# design.net
KiCad netlist of a schematic drawn in Altium Designer
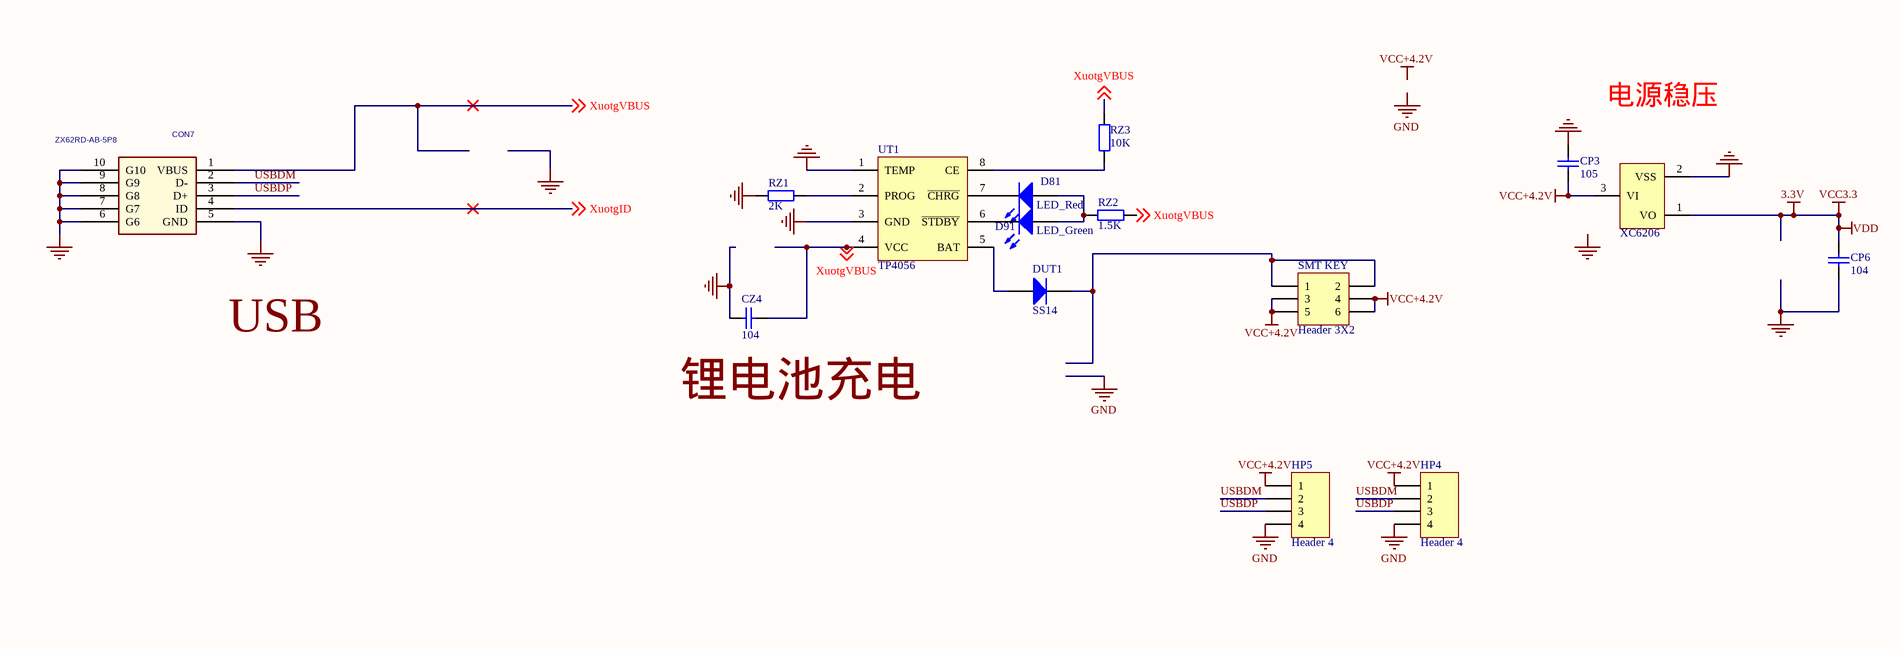
[diagram p0: 智能笔.SchDoc, top left]
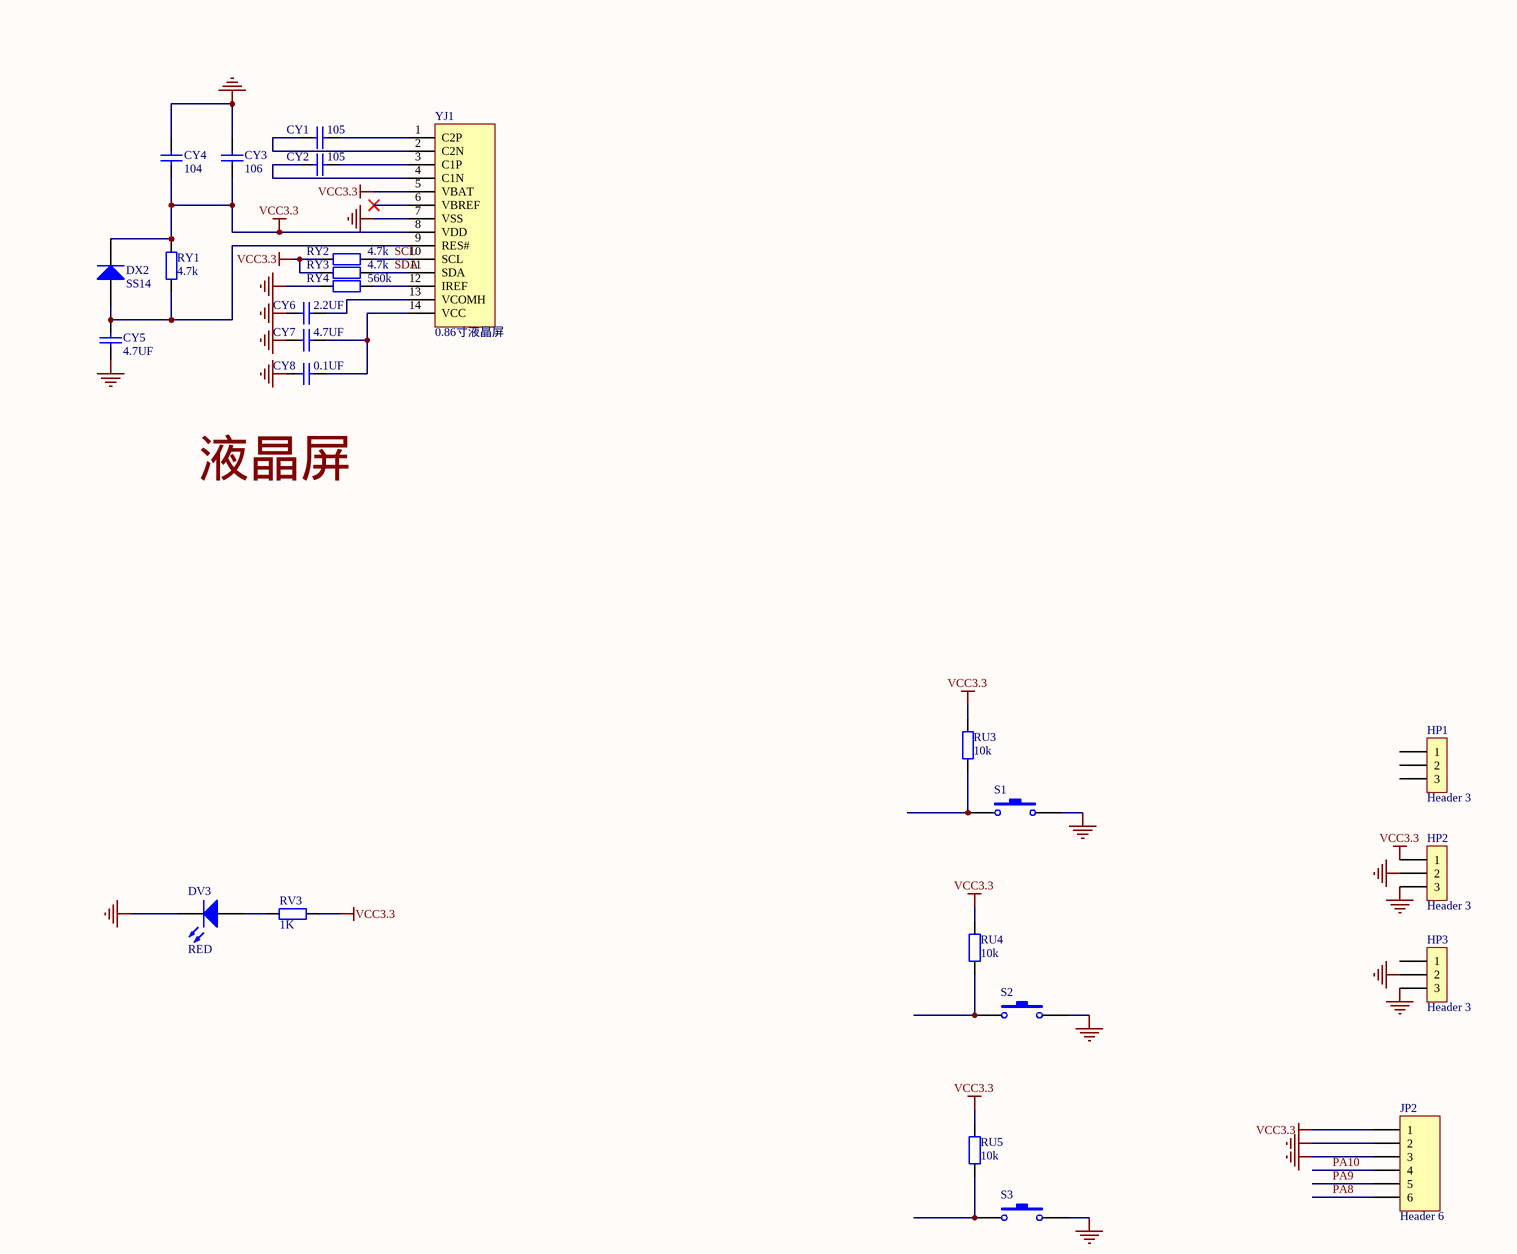
[diagram p1: 智能笔.SchDoc, top right]
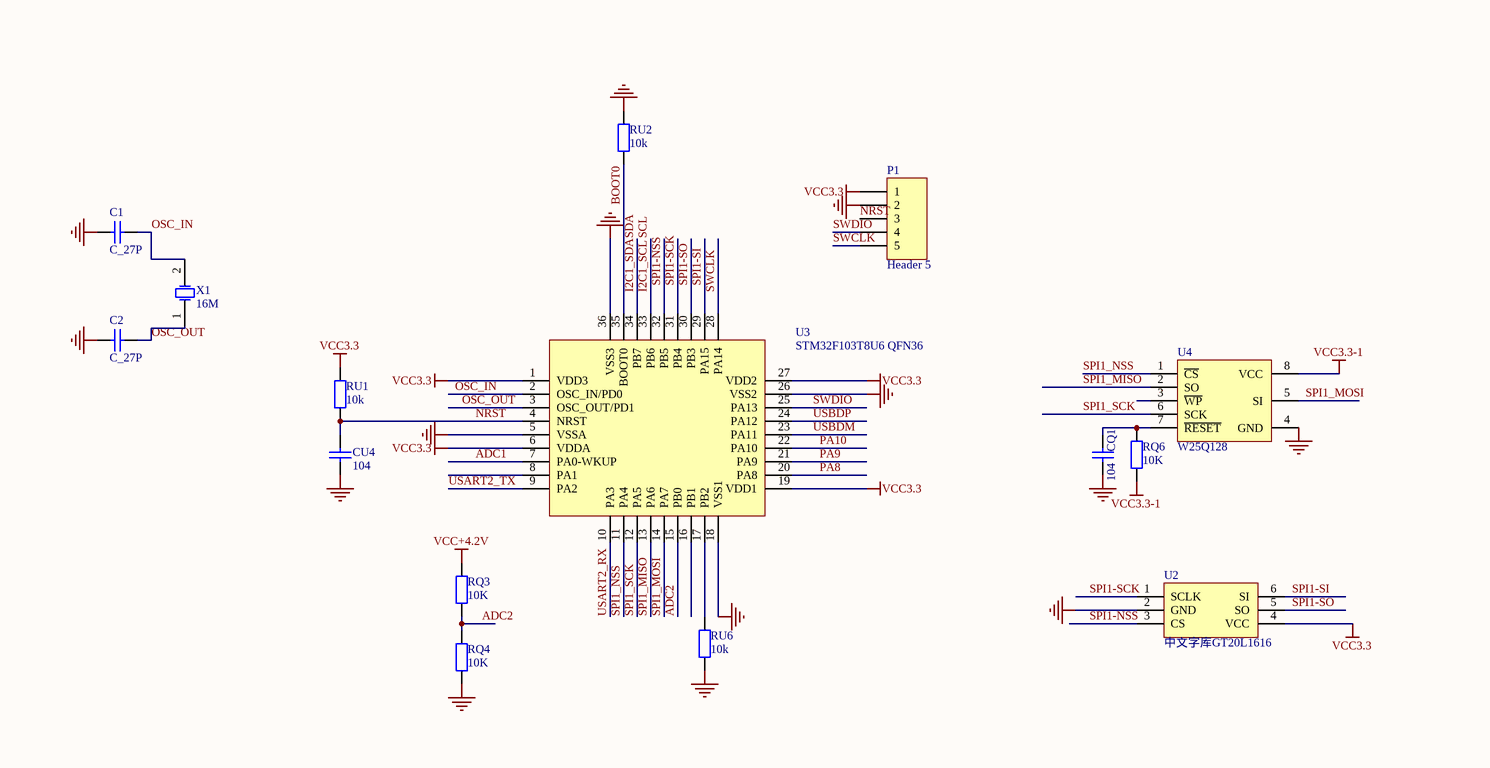
[diagram p2: 智能笔.SchDoc, bottom left]

(export (version "E")
  (design (tool "Eeschema 10.0.6"))
  (components
    (comp (ref "C1")
      (value "C_27P")
      (footprint "0402")
      (description "Capacitor")
      (fields (field (name "PUBLISHER") "Altium Limited"))
      (libsource (lib "Miscellaneous Devices") (part "Cap"))
    )
    (comp (ref "C2")
      (value "C_27P")
      (footprint "0402")
      (description "Capacitor")
      (fields (field (name "PUBLISHER") "Altium Limited"))
      (libsource (lib "Miscellaneous Devices") (part "Cap"))
    )
    (comp (ref "CON7")
      (value "ZX62RD-AB-5P8")
      (footprint "MICROUSB-B-H4")
      (libsource (lib "*") (part "ZX62RD-AB-5P8_4"))
    )
    (comp (ref "CP3")
      (value "105")
      (footprint "0402")
      (description "Capacitor")
      (fields (field (name "PUBLISHER") "Altium Limited"))
      (libsource (lib "原理图库") (part "104"))
    )
    (comp (ref "CP6")
      (value "104")
      (footprint "0402")
      (description "Capacitor")
      (fields (field (name "PUBLISHER") "Altium Limited"))
      (libsource (lib "Miscellaneous Devices") (part "Cap"))
    )
    (comp (ref "CQ1")
      (value "104")
      (footprint "0402")
      (description "Capacitor")
      (fields (field (name "PUBLISHER") "Altium Limited"))
      (libsource (lib "原理图库") (part "104"))
    )
    (comp (ref "CU4")
      (value "104")
      (footprint "0402")
      (description "Capacitor")
      (fields (field (name "PUBLISHER") "Altium Limited"))
      (libsource (lib "Miscellaneous Devices") (part "Cap"))
    )
    (comp (ref "CY1")
      (value "105")
      (footprint "0402")
      (description "Capacitor")
      (fields (field (name "PUBLISHER") "Altium Limited"))
      (libsource (lib "原理图库") (part "104"))
    )
    (comp (ref "CY2")
      (value "105")
      (footprint "0402")
      (description "Capacitor")
      (fields (field (name "PUBLISHER") "Altium Limited"))
      (libsource (lib "原理图库") (part "104"))
    )
    (comp (ref "CY3")
      (value "106")
      (footprint "0603-1")
      (description "Capacitor")
      (fields (field (name "PUBLISHER") "Altium Limited"))
      (libsource (lib "Miscellaneous Devices") (part "Cap"))
    )
    (comp (ref "CY4")
      (value "104")
      (footprint "0402")
      (description "Capacitor")
      (fields (field (name "PUBLISHER") "Altium Limited"))
      (libsource (lib "Miscellaneous Devices") (part "Cap"))
    )
    (comp (ref "CY5")
      (value "4.7UF")
      (footprint "0603-1")
      (description "Capacitor")
      (fields (field (name "PUBLISHER") "Altium Limited"))
      (libsource (lib "Miscellaneous Devices") (part "Cap"))
    )
    (comp (ref "CY6")
      (value "2.2UF")
      (footprint "0603-1")
      (description "Capacitor")
      (fields (field (name "PUBLISHER") "Altium Limited"))
      (libsource (lib "Miscellaneous Devices") (part "Cap"))
    )
    (comp (ref "CY7")
      (value "4.7UF")
      (footprint "0603-1")
      (description "Capacitor")
      (fields (field (name "PUBLISHER") "Altium Limited"))
      (libsource (lib "Miscellaneous Devices") (part "Cap"))
    )
    (comp (ref "CY8")
      (value "0.1UF")
      (footprint "0402")
      (description "Capacitor")
      (fields (field (name "PUBLISHER") "Altium Limited"))
      (libsource (lib "Miscellaneous Devices") (part "Cap"))
    )
    (comp (ref "CZ4")
      (value "104")
      (footprint "0402")
      (description "Capacitor")
      (fields (field (name "PUBLISHER") "Altium Limited"))
      (libsource (lib "原理图库") (part "104"))
    )
    (comp (ref "D81")
      (value "LED_Red")
      (footprint "0603")
      (description "Typical RED GaAs LED")
      (fields (field (name "PUBLISHER") "Altium Limited"))
      (libsource (lib "SCH原理图库") (part "LED1"))
    )
    (comp (ref "D91")
      (value "LED_Green")
      (footprint "0603")
      (description "Typical RED GaAs LED")
      (fields (field (name "PUBLISHER") "Altium Limited"))
      (libsource (lib "SCH原理图库") (part "LED1"))
    )
    (comp (ref "DUT1")
      (value "SS14")
      (footprint "DIODE_SOP")
      (description "1 Amp General Purpose Rectifier")
      (fields (field (name "PUBLISHER") "Altium Limited"))
      (libsource (lib "SCH原理图库") (part "Diode 1N4001"))
    )
    (comp (ref "DV3")
      (value "RED")
      (footprint "0603")
      (description "Typical RED GaAs LED")
      (fields (field (name "PUBLISHER") "Altium Limited"))
      (libsource (lib "SCH原理图库") (part "LED1"))
    )
    (comp (ref "DX2")
      (value "SS14")
      (footprint "DIODE_SOP")
      (description "1 Amp General Purpose Rectifier")
      (fields (field (name "PUBLISHER") "Altium Limited"))
      (libsource (lib "SCH原理图库") (part "Diode 1N4001"))
    )
    (comp (ref "HP1")
      (value "Header 3")
      (footprint "2.0 3P 焊盘")
      (description "Header, 3-Pin")
      (fields (field (name "PUBLISHER") "Altium Limited"))
      (libsource (lib "SCH原理图库") (part "Header 3"))
    )
    (comp (ref "HP2")
      (value "Header 3")
      (footprint "2.0 3P 焊盘")
      (description "Header, 3-Pin")
      (fields (field (name "PUBLISHER") "Altium Limited"))
      (libsource (lib "SCH原理图库") (part "Header 3"))
    )
    (comp (ref "HP3")
      (value "Header 3")
      (footprint "2.0 3P 焊盘")
      (description "Header, 3-Pin")
      (fields (field (name "PUBLISHER") "Altium Limited"))
      (libsource (lib "SCH原理图库") (part "Header 3"))
    )
    (comp (ref "HP4")
      (value "Header 4")
      (footprint "2.0 4P 焊盘")
      (description "Header, 4-Pin")
      (fields (field (name "PUBLISHER") "Altium Limited"))
      (libsource (lib "SCH原理图库") (part "Header 4"))
    )
    (comp (ref "HP5")
      (value "Header 4")
      (footprint "2.0 4P 焊盘")
      (description "Header, 4-Pin")
      (fields (field (name "PUBLISHER") "Altium Limited"))
      (libsource (lib "SCH原理图库") (part "Header 4"))
    )
    (comp (ref "JP2")
      (value "Header 6")
      (footprint "1.27MM  6H - 焊接")
      (description "Header, 6-Pin")
      (fields (field (name "PUBLISHER") "Altium Limited"))
      (libsource (lib "SCH原理图库") (part "Header 6"))
    )
    (comp (ref "P1")
      (value "Header 5")
      (footprint "2.0 1*5P")
      (description "Header, 5-Pin")
      (fields (field (name "PUBLISHER") "Altium Limited"))
      (libsource (lib "SCH原理图库") (part "Header 5"))
    )
    (comp (ref "RQ3")
      (value "10K")
      (footprint "0402")
      (description "Resistor")
      (fields (field (name "PUBLISHER") "Altium Limited"))
      (libsource (lib "Miscellaneous Devices") (part "Res2"))
    )
    (comp (ref "RQ4")
      (value "10K")
      (footprint "0402")
      (description "Resistor")
      (fields (field (name "PUBLISHER") "Altium Limited"))
      (libsource (lib "Miscellaneous Devices") (part "Res2"))
    )
    (comp (ref "RQ6")
      (value "10K")
      (footprint "0402")
      (description "Resistor")
      (fields (field (name "PUBLISHER") "Altium Limited"))
      (libsource (lib "Miscellaneous Devices") (part "Res2"))
    )
    (comp (ref "RU1")
      (value "10k")
      (footprint "0402")
      (description "Resistor")
      (fields (field (name "PUBLISHER") "Altium Limited"))
      (libsource (lib "Miscellaneous Devices") (part "Res2"))
    )
    (comp (ref "RU2")
      (value "10k")
      (footprint "0402")
      (description "Resistor")
      (fields (field (name "PUBLISHER") "Altium Limited"))
      (libsource (lib "") (part "Res2_1"))
    )
    (comp (ref "RU3")
      (value "10k")
      (footprint "0402")
      (description "Resistor")
      (fields (field (name "PUBLISHER") "Altium Limited"))
      (libsource (lib "") (part "Res2_1"))
    )
    (comp (ref "RU4")
      (value "10k")
      (footprint "0402")
      (description "Resistor")
      (fields (field (name "PUBLISHER") "Altium Limited"))
      (libsource (lib "") (part "Res2_1"))
    )
    (comp (ref "RU5")
      (value "10k")
      (footprint "0402")
      (description "Resistor")
      (fields (field (name "PUBLISHER") "Altium Limited"))
      (libsource (lib "") (part "Res2_1"))
    )
    (comp (ref "RU6")
      (value "10k")
      (footprint "0402")
      (description "Resistor")
      (fields (field (name "PUBLISHER") "Altium Limited"))
      (libsource (lib "Miscellaneous Devices") (part "Res2"))
    )
    (comp (ref "RV3")
      (value "1K")
      (footprint "0402")
      (description "Resistor")
      (fields (field (name "PUBLISHER") "Altium Limited"))
      (libsource (lib "") (part "Res2_2"))
    )
    (comp (ref "RY1")
      (value "4.7k")
      (footprint "0402")
      (description "Resistor")
      (fields (field (name "PUBLISHER") "Altium Limited"))
      (libsource (lib "") (part "Res2_1"))
    )
    (comp (ref "RY2")
      (value "4.7k")
      (footprint "0402")
      (description "Resistor")
      (fields (field (name "PUBLISHER") "Altium Limited"))
      (libsource (lib "") (part "Res2_2"))
    )
    (comp (ref "RY3")
      (value "4.7k")
      (footprint "0402")
      (description "Resistor")
      (fields (field (name "PUBLISHER") "Altium Limited"))
      (libsource (lib "") (part "Res2_2"))
    )
    (comp (ref "RY4")
      (value "560k")
      (footprint "0402")
      (description "Resistor")
      (fields (field (name "PUBLISHER") "Altium Limited"))
      (libsource (lib "") (part "Res2_3"))
    )
    (comp (ref "RZ1")
      (value "2K")
      (footprint "0402")
      (description "Resistor")
      (fields (field (name "PUBLISHER") "Altium Limited"))
      (libsource (lib "") (part "Res2_2"))
    )
    (comp (ref "RZ2")
      (value "1.5K")
      (footprint "0402")
      (description "Resistor")
      (fields (field (name "PUBLISHER") "Altium Limited"))
      (libsource (lib "") (part "Res2_2"))
    )
    (comp (ref "RZ3")
      (value "10K")
      (footprint "0402")
      (description "Resistor")
      (fields (field (name "PUBLISHER") "Altium Limited"))
      (libsource (lib "Miscellaneous Devices") (part "Res2"))
    )
    (comp (ref "S1")
      (value "SW-PB")
      (footprint "SW_smt4*4")
      (description "Switch")
      (fields (field (name "PUBLISHER") "Altium Limited"))
      (libsource (lib "SCH原理图库") (part "SW-PB"))
    )
    (comp (ref "S2")
      (value "SW-PB")
      (footprint "SW_smt4*4")
      (description "Switch")
      (fields (field (name "PUBLISHER") "Altium Limited"))
      (libsource (lib "SCH原理图库") (part "SW-PB"))
    )
    (comp (ref "S3")
      (value "SW-PB")
      (footprint "SW_smt4*4")
      (description "Switch")
      (fields (field (name "PUBLISHER") "Altium Limited"))
      (libsource (lib "SCH原理图库") (part "SW-PB"))
    )
    (comp (ref "SMT KEY")
      (value "Header 3X2")
      (footprint "拨动开关")
      (description "Header, 3-Pin, Dual row")
      (fields (field (name "PUBLISHER") "Altium Limited"))
      (libsource (lib "SCH原理图库") (part "Header 3X2"))
    )
    (comp (ref "U2")
      (value "中文字库GT20L1616")
      (footprint "SOT23-6")
      (libsource (lib "SCH原理图库") (part "中文字库GT20L1616"))
    )
    (comp (ref "U3")
      (value "STM32F103T8U6 QFN36")
      (footprint "QFN36")
      (libsource (lib "SCH原理图库") (part "STM32F103T8U6 QFN36"))
    )
    (comp (ref "U4")
      (value "W25Q128")
      (footprint "SST25VF016B")
      (libsource (lib "原理图库") (part "SST25VF016B"))
    )
    (comp (ref "UT1") (value "TP4056") (footprint "SOP-8P") (libsource (lib "SCH原理图库") (part "TP4056")))
    (comp (ref "X1")
      (value "16M")
      (footprint "Crystal_SOP 2016")
      (description "Crystal Oscillator")
      (fields (field (name "PUBLISHER") "Altium Limited"))
      (libsource (lib "SCH原理图库") (part "XTAL_1"))
    )
    (comp (ref "XC6206")
      (value "XC6206P332MR (662K) 3.3V/0.5A 稳压芯片")
      (footprint "SOT23-3-1")
      (libsource (lib "原理图库") (part "XC6206P332MR (662K) 3.3V/0.5A 稳压芯片"))
    )
    (comp (ref "YJ1")
      (value "0.86寸液晶屏")
      (footprint "0.86寸 oled 显示屏")
      (libsource (lib "SCH原理图库") (part "0.86寸液晶屏"))
    )
  )
  (nets
    (net (code "1") (name "/ADC1") (class "Default")
      (node (ref "U3") (pin "7") (pinfunction "PA0-WKUP_7") (pintype "passive"))
    )
    (net (code "2") (name "/ADC2") (class "Default")
      (node (ref "RQ3") (pin "2") (pinfunction "2_2") (pintype "passive"))
      (node (ref "RQ4") (pin "1") (pinfunction "1_1") (pintype "passive"))
      (node (ref "U3") (pin "15") (pinfunction "PB0_15") (pintype "passive"))
    )
    (net (code "3") (name "/BOOT0") (class "Default")
      (node (ref "RU2") (pin "1") (pinfunction "1_1") (pintype "passive"))
      (node (ref "U3") (pin "35") (pinfunction "BOOT0_35") (pintype "passive"))
    )
    (net (code "4") (name "/I2C1_SCL") (class "Default")
      (node (ref "RY2") (pin "1") (pinfunction "1_1") (pintype "passive"))
      (node (ref "U3") (pin "33") (pinfunction "PB6_33") (pintype "passive"))
      (node (ref "YJ1") (pin "10") (pinfunction "SCL_10") (pintype "passive"))
    )
    (net (code "5") (name "/I2C1_SDA") (class "Default")
      (node (ref "RY3") (pin "1") (pinfunction "1_1") (pintype "passive"))
      (node (ref "U3") (pin "34") (pinfunction "PB7_34") (pintype "passive"))
      (node (ref "YJ1") (pin "11") (pinfunction "SDA_11") (pintype "passive"))
    )
    (net (code "6") (name "/NRST") (class "Default")
      (node (ref "CU4") (pin "1") (pinfunction "1_1") (pintype "passive"))
      (node (ref "P1") (pin "3") (pinfunction "3_3") (pintype "passive"))
      (node (ref "RU1") (pin "2") (pinfunction "2_2") (pintype "passive"))
      (node (ref "U3") (pin "4") (pinfunction "NRST_4") (pintype "passive"))
    )
    (net (code "7") (name "/OSC_IN") (class "Default")
      (node (ref "C1") (pin "2") (pinfunction "2_2") (pintype "passive"))
      (node (ref "U3") (pin "2") (pinfunction "OSC_IN/PD0_2") (pintype "passive"))
      (node (ref "X1") (pin "2") (pinfunction "OSC2_2") (pintype "passive"))
    )
    (net (code "8") (name "/OSC_OUT") (class "Default")
      (node (ref "C2") (pin "2") (pinfunction "2_2") (pintype "passive"))
      (node (ref "U3") (pin "3") (pinfunction "OSC_OUT/PD1_3") (pintype "passive"))
      (node (ref "X1") (pin "1") (pinfunction "OSC1_1") (pintype "passive"))
    )
    (net (code "9") (name "/PA8") (class "Default")
      (node (ref "JP2") (pin "6") (pinfunction "6_6") (pintype "passive"))
      (node (ref "U3") (pin "20") (pinfunction "PA8_20") (pintype "passive"))
    )
    (net (code "10") (name "/PA9") (class "Default")
      (node (ref "JP2") (pin "5") (pinfunction "5_5") (pintype "passive"))
      (node (ref "U3") (pin "21") (pinfunction "PA9_21") (pintype "passive"))
    )
    (net (code "11") (name "/PA10") (class "Default")
      (node (ref "JP2") (pin "4") (pinfunction "4_4") (pintype "passive"))
      (node (ref "U3") (pin "22") (pinfunction "PA10_22") (pintype "passive"))
    )
    (net (code "12") (name "/SPI1-NSS") (class "Default")
      (node (ref "U2") (pin "3") (pinfunction "CS_3") (pintype "passive"))
      (node (ref "U3") (pin "32") (pinfunction "PB5_32") (pintype "passive"))
    )
    (net (code "13") (name "/SPI1-SCK") (class "Default")
      (node (ref "U2") (pin "1") (pinfunction "SCLK_1") (pintype "passive"))
      (node (ref "U3") (pin "31") (pinfunction "PB4_31") (pintype "passive"))
    )
    (net (code "14") (name "/SPI1-SI") (class "Default")
      (node (ref "U2") (pin "6") (pinfunction "SI_6") (pintype "passive"))
      (node (ref "U3") (pin "29") (pinfunction "PA15_29") (pintype "passive"))
    )
    (net (code "15") (name "/SPI1-SO") (class "Default")
      (node (ref "U2") (pin "5") (pinfunction "SO_5") (pintype "passive"))
      (node (ref "U3") (pin "30") (pinfunction "PB3_30") (pintype "passive"))
    )
    (net (code "16") (name "/SPI1_MISO") (class "Default")
      (node (ref "U3") (pin "13") (pinfunction "PA6_13") (pintype "passive"))
      (node (ref "U4") (pin "2") (pinfunction "SO_2") (pintype "passive"))
    )
    (net (code "17") (name "/SPI1_MOSI") (class "Default")
      (node (ref "U3") (pin "14") (pinfunction "PA7_14") (pintype "passive"))
      (node (ref "U4") (pin "5") (pinfunction "SI_5") (pintype "passive"))
    )
    (net (code "18") (name "/SPI1_NSS") (class "Default")
      (node (ref "U3") (pin "11") (pinfunction "PA4_11") (pintype "passive"))
      (node (ref "U4") (pin "1") (pinfunction "~{CS}_1") (pintype "passive"))
    )
    (net (code "19") (name "/SPI1_SCK") (class "Default")
      (node (ref "U3") (pin "12") (pinfunction "PA5_12") (pintype "passive"))
      (node (ref "U4") (pin "6") (pinfunction "SCK_6") (pintype "passive"))
    )
    (net (code "20") (name "/SWCLK") (class "Default")
      (node (ref "P1") (pin "5") (pinfunction "5_5") (pintype "passive"))
      (node (ref "U3") (pin "28") (pinfunction "PA14_28") (pintype "passive"))
    )
    (net (code "21") (name "/SWDIO") (class "Default")
      (node (ref "P1") (pin "4") (pinfunction "4_4") (pintype "passive"))
      (node (ref "U3") (pin "25") (pinfunction "PA13_25") (pintype "passive"))
    )
    (net (code "22") (name "/USART2_RX") (class "Default")
      (node (ref "U3") (pin "10") (pinfunction "PA3_10") (pintype "passive"))
    )
    (net (code "23") (name "/USART2_TX") (class "Default")
      (node (ref "U3") (pin "9") (pinfunction "PA2_9") (pintype "passive"))
    )
    (net (code "25") (name "/USBDM") (class "Default")
      (node (ref "CON7") (pin "2") (pinfunction "D-_2") (pintype "passive"))
      (node (ref "HP4") (pin "2") (pinfunction "2_2") (pintype "passive"))
      (node (ref "HP5") (pin "2") (pinfunction "2_2") (pintype "passive"))
      (node (ref "U3") (pin "23") (pinfunction "PA11_23") (pintype "passive"))
    )
    (net (code "26") (name "/USBDP") (class "Default")
      (node (ref "CON7") (pin "3") (pinfunction "D+_3") (pintype "passive"))
      (node (ref "HP4") (pin "3") (pinfunction "3_3") (pintype "passive"))
      (node (ref "HP5") (pin "3") (pinfunction "3_3") (pintype "passive"))
      (node (ref "U3") (pin "24") (pinfunction "PA12_24") (pintype "passive"))
    )
    (net (code "29") (name "3.3V") (class "Default")
      (node (ref "CP6") (pin "1") (pinfunction "1_1") (pintype "passive"))
      (node (ref "CY3") (pin "1") (pinfunction "1_1") (pintype "passive"))
      (node (ref "CY4") (pin "1") (pinfunction "1_1") (pintype "passive"))
      (node (ref "DX2") (pin "2") (pinfunction "K_2") (pintype "passive"))
      (node (ref "HP2") (pin "1") (pinfunction "1_1") (pintype "passive"))
      (node (ref "JP2") (pin "1") (pinfunction "1_1") (pintype "passive"))
      (node (ref "P1") (pin "1") (pinfunction "1_1") (pintype "passive"))
      (node (ref "RU1") (pin "1") (pinfunction "1_1") (pintype "passive"))
      (node (ref "RU3") (pin "2") (pinfunction "2_2") (pintype "passive"))
      (node (ref "RU4") (pin "2") (pinfunction "2_2") (pintype "passive"))
      (node (ref "RU5") (pin "2") (pinfunction "2_2") (pintype "passive"))
      (node (ref "RV3") (pin "1") (pinfunction "1_1") (pintype "passive"))
      (node (ref "RY1") (pin "2") (pinfunction "2_2") (pintype "passive"))
      (node (ref "RY2") (pin "2") (pinfunction "2_2") (pintype "passive"))
      (node (ref "RY3") (pin "2") (pinfunction "2_2") (pintype "passive"))
      (node (ref "U2") (pin "4") (pinfunction "VCC_4") (pintype "passive"))
      (node (ref "U3") (pin "1") (pinfunction "VDD3_1") (pintype "passive"))
      (node (ref "U3") (pin "19") (pinfunction "VDD1_19") (pintype "passive"))
      (node (ref "U3") (pin "27") (pinfunction "VDD2_27") (pintype "passive"))
      (node (ref "U3") (pin "6") (pinfunction "VDDA_6") (pintype "passive"))
      (node (ref "XC6206") (pin "1") (pinfunction "VO_1") (pintype "passive"))
      (node (ref "YJ1") (pin "5") (pinfunction "VBAT_5") (pintype "passive"))
      (node (ref "YJ1") (pin "8") (pinfunction "VDD_8") (pintype "passive"))
    )
    (net (code "30") (name "GND") (class "Default")
      (node (ref "C1") (pin "1") (pinfunction "1_1") (pintype "passive"))
      (node (ref "C2") (pin "1") (pinfunction "1_1") (pintype "passive"))
      (node (ref "CON7") (pin "10") (pinfunction "G10_10") (pintype "passive"))
      (node (ref "CON7") (pin "5") (pinfunction "GND_5") (pintype "passive"))
      (node (ref "CON7") (pin "6") (pinfunction "G6_6") (pintype "passive"))
      (node (ref "CON7") (pin "7") (pinfunction "G7_7") (pintype "passive"))
      (node (ref "CON7") (pin "8") (pinfunction "G8_8") (pintype "passive"))
      (node (ref "CON7") (pin "9") (pinfunction "G9_9") (pintype "passive"))
      (node (ref "CP3") (pin "1") (pinfunction "1_1") (pintype "passive"))
      (node (ref "CP6") (pin "2") (pinfunction "2_2") (pintype "passive"))
      (node (ref "CQ1") (pin "2") (pinfunction "2_2") (pintype "passive"))
      (node (ref "CU4") (pin "2") (pinfunction "2_2") (pintype "passive"))
      (node (ref "CY3") (pin "2") (pinfunction "2_2") (pintype "passive"))
      (node (ref "CY4") (pin "2") (pinfunction "2_2") (pintype "passive"))
      (node (ref "CY5") (pin "1") (pinfunction "1_1") (pintype "passive"))
      (node (ref "CY6") (pin "2") (pinfunction "2_2") (pintype "passive"))
      (node (ref "CY7") (pin "2") (pinfunction "2_2") (pintype "passive"))
      (node (ref "CY8") (pin "2") (pinfunction "2_2") (pintype "passive"))
      (node (ref "CZ4") (pin "1") (pinfunction "1_1") (pintype "passive"))
      (node (ref "DV3") (pin "2") (pinfunction "K_2") (pintype "passive"))
      (node (ref "HP2") (pin "2") (pinfunction "2_2") (pintype "passive"))
      (node (ref "HP2") (pin "3") (pinfunction "3_3") (pintype "passive"))
      (node (ref "HP3") (pin "2") (pinfunction "2_2") (pintype "passive"))
      (node (ref "HP3") (pin "3") (pinfunction "3_3") (pintype "passive"))
      (node (ref "HP4") (pin "4") (pinfunction "4_4") (pintype "passive"))
      (node (ref "HP5") (pin "4") (pinfunction "4_4") (pintype "passive"))
      (node (ref "JP2") (pin "2") (pinfunction "2_2") (pintype "passive"))
      (node (ref "JP2") (pin "3") (pinfunction "3_3") (pintype "passive"))
      (node (ref "P1") (pin "2") (pinfunction "2_2") (pintype "passive"))
      (node (ref "RQ4") (pin "2") (pinfunction "2_2") (pintype "passive"))
      (node (ref "RU2") (pin "2") (pinfunction "2_2") (pintype "passive"))
      (node (ref "RU6") (pin "2") (pinfunction "2_2") (pintype "passive"))
      (node (ref "RY4") (pin "1") (pinfunction "1_1") (pintype "passive"))
      (node (ref "RZ1") (pin "2") (pinfunction "2_2") (pintype "passive"))
      (node (ref "S1") (pin "2") (pinfunction "2_2") (pintype "passive"))
      (node (ref "S2") (pin "2") (pinfunction "2_2") (pintype "passive"))
      (node (ref "S3") (pin "2") (pinfunction "2_2") (pintype "passive"))
      (node (ref "U2") (pin "2") (pinfunction "GND_2") (pintype "passive"))
      (node (ref "U3") (pin "18") (pinfunction "VSS1_18") (pintype "passive"))
      (node (ref "U3") (pin "26") (pinfunction "VSS2_26") (pintype "passive"))
      (node (ref "U3") (pin "36") (pinfunction "VSS3_36") (pintype "passive"))
      (node (ref "U3") (pin "5") (pinfunction "VSSA_5") (pintype "passive"))
      (node (ref "U4") (pin "4") (pinfunction "GND_4") (pintype "passive"))
      (node (ref "UT1") (pin "1") (pinfunction "TEMP_1") (pintype "passive"))
      (node (ref "UT1") (pin "3") (pinfunction "GND_3") (pintype "passive"))
      (node (ref "XC6206") (pin "2") (pinfunction "VSS_2") (pintype "passive"))
      (node (ref "YJ1") (pin "7") (pinfunction "VSS_7") (pintype "passive"))
    )
    (net (code "31") (name "Net-(D81-A)") (class "Default")
      (node (ref "D81") (pin "1") (pinfunction "A_1") (pintype "passive"))
      (node (ref "D91") (pin "1") (pinfunction "A_1") (pintype "passive"))
      (node (ref "RZ2") (pin "2") (pinfunction "2_2") (pintype "passive"))
    )
    (net (code "32") (name "Net-(D81-K)") (class "Default")
      (node (ref "D81") (pin "2") (pinfunction "K_2") (pintype "passive"))
      (node (ref "UT1") (pin "7") (pinfunction "~{CHRG}_7") (pintype "passive"))
    )
    (net (code "33") (name "Net-(D91-K)") (class "Default")
      (node (ref "D91") (pin "2") (pinfunction "K_2") (pintype "passive"))
      (node (ref "UT1") (pin "6") (pinfunction "~{STDBY}_6") (pintype "passive"))
    )
    (net (code "34") (name "Net-(DUT1-A)") (class "Default")
      (node (ref "DUT1") (pin "1") (pinfunction "A_1") (pintype "passive"))
      (node (ref "UT1") (pin "5") (pinfunction "BAT_5") (pintype "passive"))
    )
    (net (code "35") (name "Net-(DUT1-K)") (class "Default")
      (node (ref "DUT1") (pin "2") (pinfunction "K_2") (pintype "passive"))
      (node (ref "SMT KEY") (pin "1") (pinfunction "1_1") (pintype "passive"))
      (node (ref "SMT KEY") (pin "2") (pinfunction "2_2") (pintype "passive"))
    )
    (net (code "36") (name "Net-(DV3-A)") (class "Default")
      (node (ref "DV3") (pin "1") (pinfunction "A_1") (pintype "passive"))
      (node (ref "RV3") (pin "2") (pinfunction "2_2") (pintype "passive"))
    )
    (net (code "37") (name "Net-(DX2-A)") (class "Default")
      (node (ref "CY5") (pin "2") (pinfunction "2_2") (pintype "passive"))
      (node (ref "DX2") (pin "1") (pinfunction "A_1") (pintype "passive"))
      (node (ref "RY1") (pin "1") (pinfunction "1_1") (pintype "passive"))
      (node (ref "YJ1") (pin "9") (pinfunction "RES#_9") (pintype "passive"))
    )
    (net (code "38") (name "Net-(RU3-Pad1)") (class "Default")
      (node (ref "RU3") (pin "1") (pinfunction "1_1") (pintype "passive"))
      (node (ref "S1") (pin "1") (pinfunction "1_1") (pintype "passive"))
    )
    (net (code "39") (name "Net-(RU4-Pad1)") (class "Default")
      (node (ref "RU4") (pin "1") (pinfunction "1_1") (pintype "passive"))
      (node (ref "S2") (pin "1") (pinfunction "1_1") (pintype "passive"))
    )
    (net (code "40") (name "Net-(RU5-Pad1)") (class "Default")
      (node (ref "RU5") (pin "1") (pinfunction "1_1") (pintype "passive"))
      (node (ref "S3") (pin "1") (pinfunction "1_1") (pintype "passive"))
    )
    (net (code "41") (name "Net-(U3-PB2)") (class "Default")
      (node (ref "RU6") (pin "1") (pinfunction "1_1") (pintype "passive"))
      (node (ref "U3") (pin "17") (pinfunction "PB2_17") (pintype "passive"))
    )
    (net (code "42") (name "Net-(U4-~{RESET})") (class "Default")
      (node (ref "CQ1") (pin "1") (pinfunction "1_1") (pintype "passive"))
      (node (ref "RQ6") (pin "1") (pinfunction "1_1") (pintype "passive"))
      (node (ref "U4") (pin "7") (pinfunction "~{RESET}_7") (pintype "passive"))
    )
    (net (code "43") (name "Net-(UT1-CE)") (class "Default")
      (node (ref "RZ3") (pin "2") (pinfunction "2_2") (pintype "passive"))
      (node (ref "UT1") (pin "8") (pinfunction "CE_8") (pintype "passive"))
    )
    (net (code "44") (name "Net-(UT1-PROG)") (class "Default")
      (node (ref "RZ1") (pin "1") (pinfunction "1_1") (pintype "passive"))
      (node (ref "UT1") (pin "2") (pinfunction "PROG_2") (pintype "passive"))
    )
    (net (code "45") (name "Net-(YJ1-C1N)") (class "Default")
      (node (ref "CY2") (pin "2") (pinfunction "2_2") (pintype "passive"))
      (node (ref "YJ1") (pin "4") (pinfunction "C1N_4") (pintype "passive"))
    )
    (net (code "46") (name "Net-(YJ1-C1P)") (class "Default")
      (node (ref "CY2") (pin "1") (pinfunction "1_1") (pintype "passive"))
      (node (ref "YJ1") (pin "3") (pinfunction "C1P_3") (pintype "passive"))
    )
    (net (code "47") (name "Net-(YJ1-C2N)") (class "Default")
      (node (ref "CY1") (pin "2") (pinfunction "2_2") (pintype "passive"))
      (node (ref "YJ1") (pin "2") (pinfunction "C2N_2") (pintype "passive"))
    )
    (net (code "48") (name "Net-(YJ1-C2P)") (class "Default")
      (node (ref "CY1") (pin "1") (pinfunction "1_1") (pintype "passive"))
      (node (ref "YJ1") (pin "1") (pinfunction "C2P_1") (pintype "passive"))
    )
    (net (code "49") (name "Net-(YJ1-IREF)") (class "Default")
      (node (ref "RY4") (pin "2") (pinfunction "2_2") (pintype "passive"))
      (node (ref "YJ1") (pin "12") (pinfunction "IREF_12") (pintype "passive"))
    )
    (net (code "50") (name "Net-(YJ1-VCC)") (class "Default")
      (node (ref "CY7") (pin "1") (pinfunction "1_1") (pintype "passive"))
      (node (ref "CY8") (pin "1") (pinfunction "1_1") (pintype "passive"))
      (node (ref "YJ1") (pin "14") (pinfunction "VCC_14") (pintype "passive"))
    )
    (net (code "51") (name "Net-(YJ1-VCOMH)") (class "Default")
      (node (ref "CY6") (pin "1") (pinfunction "1_1") (pintype "passive"))
      (node (ref "YJ1") (pin "13") (pinfunction "VCOMH_13") (pintype "passive"))
    )
    (net (code "52") (name "VCC+4.2V") (class "Default")
      (node (ref "CP3") (pin "2") (pinfunction "2_2") (pintype "passive"))
      (node (ref "HP4") (pin "1") (pinfunction "1_1") (pintype "passive"))
      (node (ref "HP5") (pin "1") (pinfunction "1_1") (pintype "passive"))
      (node (ref "RQ3") (pin "1") (pinfunction "1_1") (pintype "passive"))
      (node (ref "SMT KEY") (pin "3") (pinfunction "3_3") (pintype "passive"))
      (node (ref "SMT KEY") (pin "4") (pinfunction "4_4") (pintype "passive"))
      (node (ref "SMT KEY") (pin "5") (pinfunction "5_5") (pintype "passive"))
      (node (ref "SMT KEY") (pin "6") (pinfunction "6_6") (pintype "passive"))
      (node (ref "XC6206") (pin "3") (pinfunction "VI_3") (pintype "passive"))
    )
    (net (code "53") (name "VCC3.3-1") (class "Default")
      (node (ref "RQ6") (pin "2") (pinfunction "2_2") (pintype "passive"))
      (node (ref "U4") (pin "8") (pinfunction "VCC_8") (pintype "passive"))
    )
    (net (code "54") (name "XuotgID") (class "Default")
      (node (ref "CON7") (pin "4") (pinfunction "ID_4") (pintype "passive"))
    )
    (net (code "55") (name "XuotgVBUS") (class "Default")
      (node (ref "CON7") (pin "1") (pinfunction "VBUS_1") (pintype "passive"))
      (node (ref "CZ4") (pin "2") (pinfunction "2_2") (pintype "passive"))
      (node (ref "RZ2") (pin "1") (pinfunction "1_1") (pintype "passive"))
      (node (ref "RZ3") (pin "1") (pinfunction "1_1") (pintype "passive"))
      (node (ref "UT1") (pin "4") (pinfunction "VCC_4") (pintype "passive"))
    )
    (net (code "56") (name "unconnected-(HP1-Pad1)") (class "Default")
      (node (ref "HP1") (pin "1") (pinfunction "1_1") (pintype "passive"))
    )
    (net (code "57") (name "unconnected-(HP1-Pad2)") (class "Default")
      (node (ref "HP1") (pin "2") (pinfunction "2_2") (pintype "passive"))
    )
    (net (code "58") (name "unconnected-(HP1-Pad3)") (class "Default")
      (node (ref "HP1") (pin "3") (pinfunction "3_3") (pintype "passive"))
    )
    (net (code "59") (name "unconnected-(HP3-Pad1)") (class "Default")
      (node (ref "HP3") (pin "1") (pinfunction "1_1") (pintype "passive"))
    )
    (net (code "60") (name "unconnected-(U3-PA1-Pad8)") (class "Default")
      (node (ref "U3") (pin "8") (pinfunction "PA1_8") (pintype "passive"))
    )
    (net (code "61") (name "unconnected-(U3-PB1-Pad16)") (class "Default")
      (node (ref "U3") (pin "16") (pinfunction "PB1_16") (pintype "passive"))
    )
    (net (code "62") (name "unconnected-(U4-~{WP}-Pad3)") (class "Default")
      (node (ref "U4") (pin "3") (pinfunction "~{WP}_3") (pintype "passive"))
    )
    (net (code "63") (name "unconnected-(YJ1-VBREF-Pad6)") (class "Default")
      (node (ref "YJ1") (pin "6") (pinfunction "VBREF_6") (pintype "passive+no_connect"))
    )
  )
)
